# CHIP_SHIELD.net
KiCad netlist of a schematic drawn in EAGLE
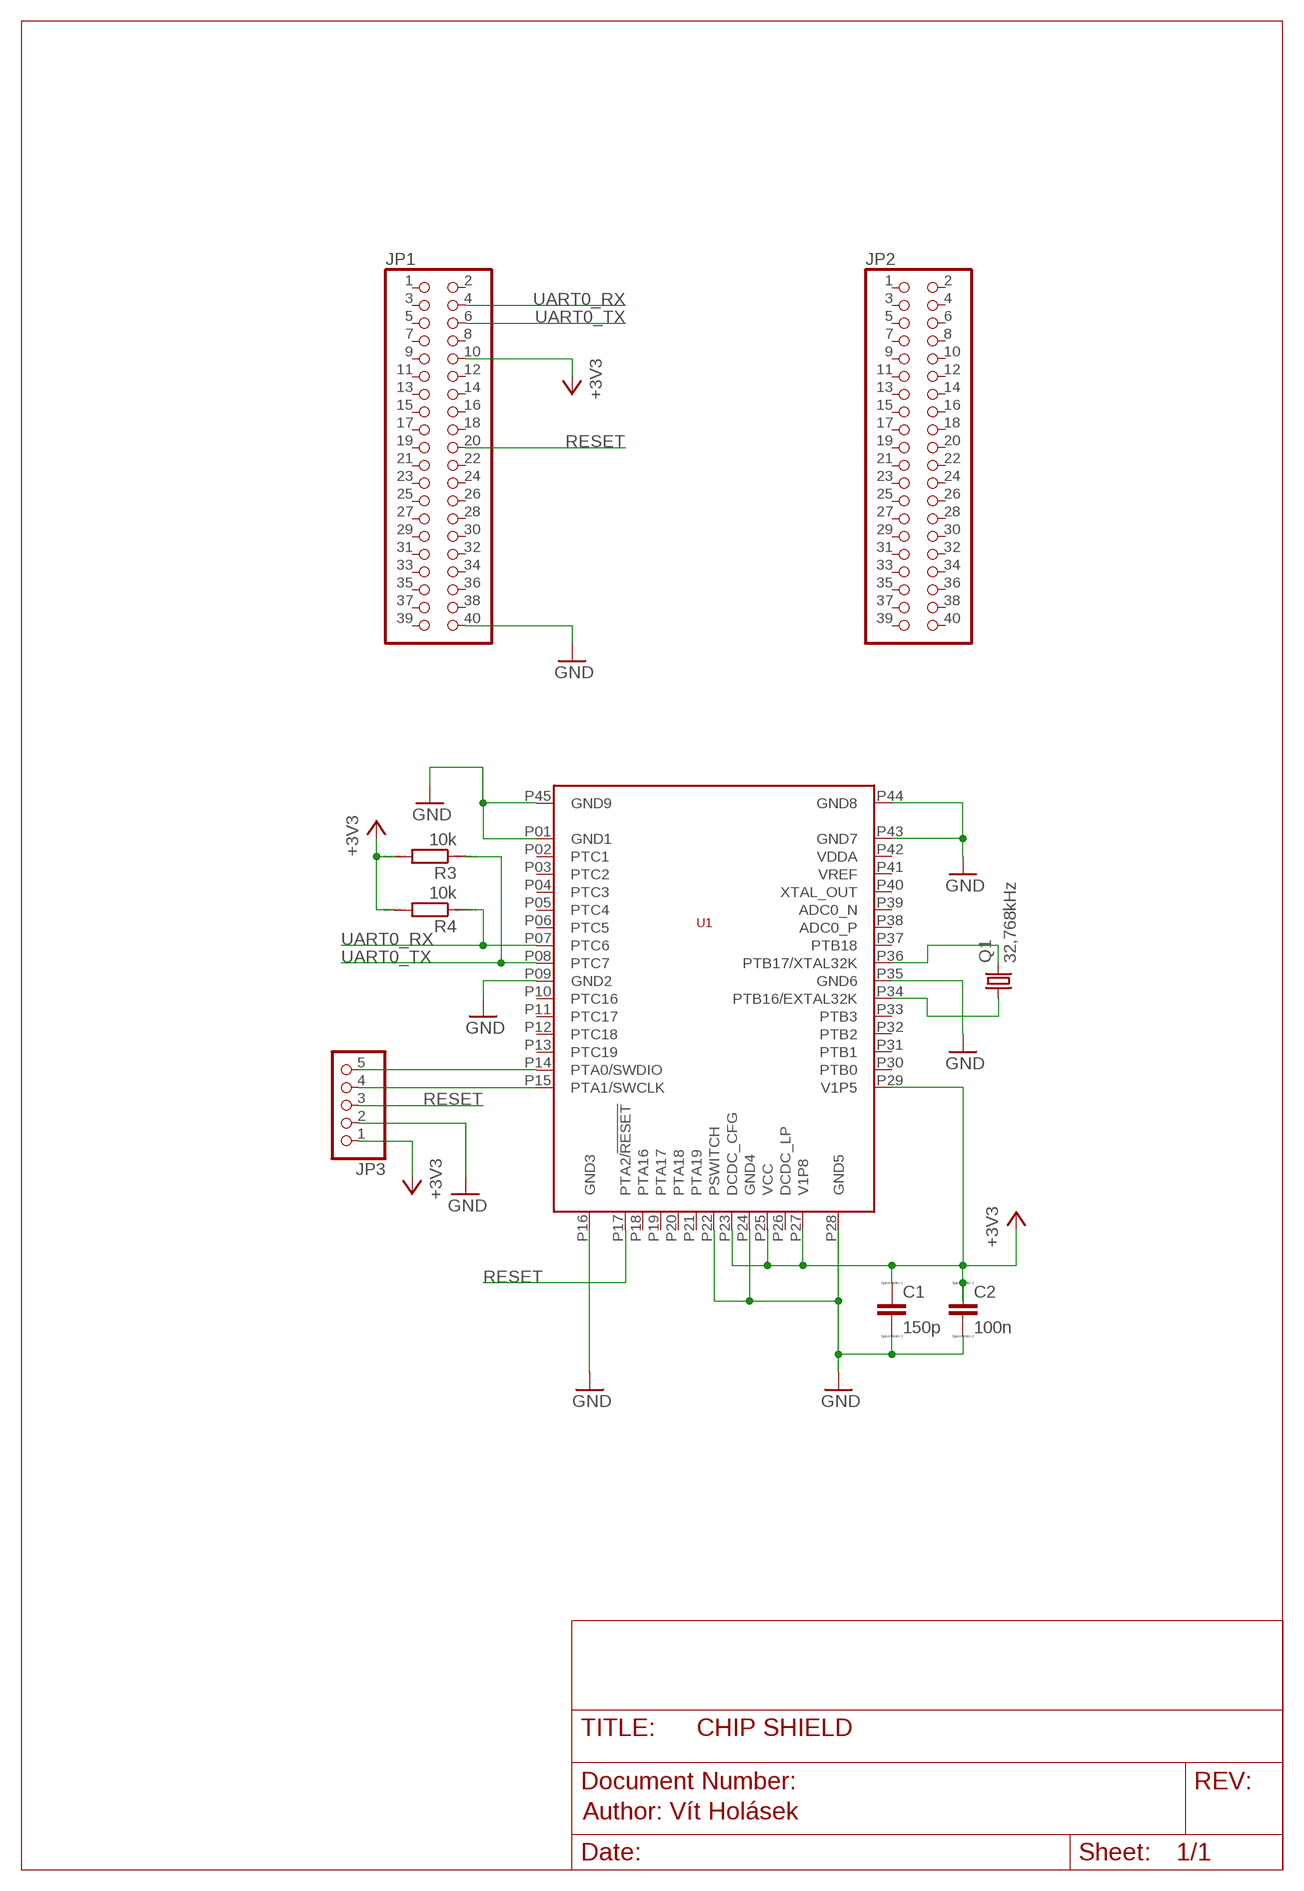
[diagram p0: schematic, sheet 1]

(export (version "E")
  (design (tool "Eeschema 10.0.6"))
  (components
    (comp (ref "C1")
      (value "150p")
      (footprint "eagle-import:C0402")
      (libsource (lib "eagle-import") (part "CC0402"))
    )
    (comp (ref "C2")
      (value "100n")
      (footprint "eagle-import:C0402")
      (libsource (lib "eagle-import") (part "CC0402"))
    )
    (comp (ref "JP1")
      (value "PINHD-2X20")
      (footprint "eagle-import:2X20")
      (libsource (lib "eagle-import") (part "PINHD-2X20"))
    )
    (comp (ref "JP2")
      (value "PINHD-2X20")
      (footprint "eagle-import:2X20")
      (libsource (lib "eagle-import") (part "PINHD-2X20"))
    )
    (comp (ref "JP3")
      (value "PINHD-1X5")
      (footprint "eagle-import:1X05")
      (libsource (lib "eagle-import") (part "PINHD-1X5"))
    )
    (comp (ref "Q1")
      (value "32,768kHz")
      (footprint "eagle-import:MC-306")
      (fields (field (name "MPN") "MC-306 60.0KHZ  100PPM ,12.5PF"))
      (libsource (lib "eagle-import") (part "MC-306"))
    )
    (comp (ref "R3")
      (value "10k")
      (footprint "eagle-import:R0402")
      (libsource (lib "eagle-import") (part "RR0402"))
    )
    (comp (ref "R4")
      (value "10k")
      (footprint "eagle-import:R0402")
      (libsource (lib "eagle-import") (part "RR0402"))
    )
    (comp (ref "U1")
      (value "R41Z-T")
      (footprint "eagle-import:R41Z")
      (libsource (lib "eagle-import") (part "R41Z-T"))
    )
  )
  (nets
    (net (code "1") (name "+3V3") (class "Default")
      (node (ref "C1") (pin "1") (pinfunction "1_1") (pintype "passive"))
      (node (ref "C2") (pin "1") (pinfunction "1_1") (pintype "passive"))
      (node (ref "JP1") (pin "10") (pinfunction "10_10") (pintype "passive"))
      (node (ref "JP3") (pin "1") (pinfunction "1_1") (pintype "passive"))
      (node (ref "R3") (pin "2") (pinfunction "2_2") (pintype "passive"))
      (node (ref "R4") (pin "2") (pinfunction "2_2") (pintype "passive"))
      (node (ref "U1") (pin "P23") (pinfunction "DCDC_CFG_P23") (pintype "bidirectional"))
      (node (ref "U1") (pin "P25") (pinfunction "VCC_P25") (pintype "bidirectional"))
      (node (ref "U1") (pin "P27") (pinfunction "V1P8_P27") (pintype "bidirectional"))
      (node (ref "U1") (pin "P29") (pinfunction "V1P5_P29") (pintype "bidirectional"))
    )
    (net (code "2") (name "/RESET") (class "Default")
      (node (ref "JP1") (pin "20") (pinfunction "20_20") (pintype "passive"))
      (node (ref "JP3") (pin "3") (pinfunction "3_3") (pintype "passive"))
      (node (ref "U1") (pin "P17") (pinfunction "PTA2/~{RESET}_P17") (pintype "bidirectional"))
    )
    (net (code "3") (name "/UART0_RX") (class "Default")
      (node (ref "JP1") (pin "4") (pinfunction "4_4") (pintype "passive"))
      (node (ref "R4") (pin "1") (pinfunction "1_1") (pintype "passive"))
      (node (ref "U1") (pin "P07") (pinfunction "PTC6_P07") (pintype "bidirectional"))
    )
    (net (code "4") (name "/UART0_TX") (class "Default")
      (node (ref "JP1") (pin "6") (pinfunction "6_6") (pintype "passive"))
      (node (ref "R3") (pin "1") (pinfunction "1_1") (pintype "passive"))
      (node (ref "U1") (pin "P08") (pinfunction "PTC7_P08") (pintype "bidirectional"))
    )
    (net (code "5") (name "GND") (class "Default")
      (node (ref "C1") (pin "2") (pinfunction "2_2") (pintype "passive"))
      (node (ref "C2") (pin "2") (pinfunction "2_2") (pintype "passive"))
      (node (ref "JP1") (pin "40") (pinfunction "40_40") (pintype "passive"))
      (node (ref "JP3") (pin "2") (pinfunction "2_2") (pintype "passive"))
      (node (ref "U1") (pin "P01") (pinfunction "GND1_P01") (pintype "bidirectional"))
      (node (ref "U1") (pin "P09") (pinfunction "GND2_P09") (pintype "bidirectional"))
      (node (ref "U1") (pin "P16") (pinfunction "GND3_P16") (pintype "bidirectional"))
      (node (ref "U1") (pin "P22") (pinfunction "PSWITCH_P22") (pintype "bidirectional"))
      (node (ref "U1") (pin "P24") (pinfunction "GND4_P24") (pintype "bidirectional"))
      (node (ref "U1") (pin "P28") (pinfunction "GND5_P28") (pintype "bidirectional"))
      (node (ref "U1") (pin "P35") (pinfunction "GND6_P35") (pintype "bidirectional"))
      (node (ref "U1") (pin "P43") (pinfunction "GND7_P43") (pintype "bidirectional"))
      (node (ref "U1") (pin "P44") (pinfunction "GND8_P44") (pintype "bidirectional"))
      (node (ref "U1") (pin "P45") (pinfunction "GND9_P45") (pintype "bidirectional"))
    )
    (net (code "6") (name "Net-(Q1-2)") (class "Default")
      (node (ref "Q1") (pin "4") (pinfunction "2_4") (pintype "passive"))
      (node (ref "U1") (pin "P36") (pinfunction "PTB17/XTAL32K_P36") (pintype "bidirectional"))
    )
    (net (code "7") (name "Net-(U1-PTA0{slash}SWDIO)") (class "Default")
      (node (ref "JP3") (pin "5") (pinfunction "5_5") (pintype "passive"))
      (node (ref "U1") (pin "P14") (pinfunction "PTA0/SWDIO_P14") (pintype "bidirectional"))
    )
    (net (code "8") (name "Net-(U1-PTA1{slash}SWCLK)") (class "Default")
      (node (ref "JP3") (pin "4") (pinfunction "4_4") (pintype "passive"))
      (node (ref "U1") (pin "P15") (pinfunction "PTA1/SWCLK_P15") (pintype "bidirectional"))
    )
    (net (code "9") (name "Net-(U1-PTB16{slash}EXTAL32K)") (class "Default")
      (node (ref "Q1") (pin "1") (pinfunction "1_1") (pintype "passive"))
      (node (ref "U1") (pin "P34") (pinfunction "PTB16/EXTAL32K_P34") (pintype "bidirectional"))
    )
    (net (code "10") (name "unconnected-(JP1-Pad1)") (class "Default")
      (node (ref "JP1") (pin "1") (pinfunction "1_1") (pintype "passive"))
    )
    (net (code "11") (name "unconnected-(JP1-Pad2)") (class "Default")
      (node (ref "JP1") (pin "2") (pinfunction "2_2") (pintype "passive"))
    )
    (net (code "12") (name "unconnected-(JP1-Pad3)") (class "Default")
      (node (ref "JP1") (pin "3") (pinfunction "3_3") (pintype "passive"))
    )
    (net (code "13") (name "unconnected-(JP1-Pad5)") (class "Default")
      (node (ref "JP1") (pin "5") (pinfunction "5_5") (pintype "passive"))
    )
    (net (code "14") (name "unconnected-(JP1-Pad7)") (class "Default")
      (node (ref "JP1") (pin "7") (pinfunction "7_7") (pintype "passive"))
    )
    (net (code "15") (name "unconnected-(JP1-Pad8)") (class "Default")
      (node (ref "JP1") (pin "8") (pinfunction "8_8") (pintype "passive"))
    )
    (net (code "16") (name "unconnected-(JP1-Pad9)") (class "Default")
      (node (ref "JP1") (pin "9") (pinfunction "9_9") (pintype "passive"))
    )
    (net (code "17") (name "unconnected-(JP1-Pad11)") (class "Default")
      (node (ref "JP1") (pin "11") (pinfunction "11_11") (pintype "passive"))
    )
    (net (code "18") (name "unconnected-(JP1-Pad12)") (class "Default")
      (node (ref "JP1") (pin "12") (pinfunction "12_12") (pintype "passive"))
    )
    (net (code "19") (name "unconnected-(JP1-Pad13)") (class "Default")
      (node (ref "JP1") (pin "13") (pinfunction "13_13") (pintype "passive"))
    )
    (net (code "20") (name "unconnected-(JP1-Pad14)") (class "Default")
      (node (ref "JP1") (pin "14") (pinfunction "14_14") (pintype "passive"))
    )
    (net (code "21") (name "unconnected-(JP1-Pad15)") (class "Default")
      (node (ref "JP1") (pin "15") (pinfunction "15_15") (pintype "passive"))
    )
    (net (code "22") (name "unconnected-(JP1-Pad16)") (class "Default")
      (node (ref "JP1") (pin "16") (pinfunction "16_16") (pintype "passive"))
    )
    (net (code "23") (name "unconnected-(JP1-Pad17)") (class "Default")
      (node (ref "JP1") (pin "17") (pinfunction "17_17") (pintype "passive"))
    )
    (net (code "24") (name "unconnected-(JP1-Pad18)") (class "Default")
      (node (ref "JP1") (pin "18") (pinfunction "18_18") (pintype "passive"))
    )
    (net (code "25") (name "unconnected-(JP1-Pad19)") (class "Default")
      (node (ref "JP1") (pin "19") (pinfunction "19_19") (pintype "passive"))
    )
    (net (code "26") (name "unconnected-(JP1-Pad21)") (class "Default")
      (node (ref "JP1") (pin "21") (pinfunction "21_21") (pintype "passive"))
    )
    (net (code "27") (name "unconnected-(JP1-Pad22)") (class "Default")
      (node (ref "JP1") (pin "22") (pinfunction "22_22") (pintype "passive"))
    )
    (net (code "28") (name "unconnected-(JP1-Pad23)") (class "Default")
      (node (ref "JP1") (pin "23") (pinfunction "23_23") (pintype "passive"))
    )
    (net (code "29") (name "unconnected-(JP1-Pad24)") (class "Default")
      (node (ref "JP1") (pin "24") (pinfunction "24_24") (pintype "passive"))
    )
    (net (code "30") (name "unconnected-(JP1-Pad25)") (class "Default")
      (node (ref "JP1") (pin "25") (pinfunction "25_25") (pintype "passive"))
    )
    (net (code "31") (name "unconnected-(JP1-Pad26)") (class "Default")
      (node (ref "JP1") (pin "26") (pinfunction "26_26") (pintype "passive"))
    )
    (net (code "32") (name "unconnected-(JP1-Pad27)") (class "Default")
      (node (ref "JP1") (pin "27") (pinfunction "27_27") (pintype "passive"))
    )
    (net (code "33") (name "unconnected-(JP1-Pad28)") (class "Default")
      (node (ref "JP1") (pin "28") (pinfunction "28_28") (pintype "passive"))
    )
    (net (code "34") (name "unconnected-(JP1-Pad29)") (class "Default")
      (node (ref "JP1") (pin "29") (pinfunction "29_29") (pintype "passive"))
    )
    (net (code "35") (name "unconnected-(JP1-Pad30)") (class "Default")
      (node (ref "JP1") (pin "30") (pinfunction "30_30") (pintype "passive"))
    )
    (net (code "36") (name "unconnected-(JP1-Pad31)") (class "Default")
      (node (ref "JP1") (pin "31") (pinfunction "31_31") (pintype "passive"))
    )
    (net (code "37") (name "unconnected-(JP1-Pad32)") (class "Default")
      (node (ref "JP1") (pin "32") (pinfunction "32_32") (pintype "passive"))
    )
    (net (code "38") (name "unconnected-(JP1-Pad33)") (class "Default")
      (node (ref "JP1") (pin "33") (pinfunction "33_33") (pintype "passive"))
    )
    (net (code "39") (name "unconnected-(JP1-Pad34)") (class "Default")
      (node (ref "JP1") (pin "34") (pinfunction "34_34") (pintype "passive"))
    )
    (net (code "40") (name "unconnected-(JP1-Pad35)") (class "Default")
      (node (ref "JP1") (pin "35") (pinfunction "35_35") (pintype "passive"))
    )
    (net (code "41") (name "unconnected-(JP1-Pad36)") (class "Default")
      (node (ref "JP1") (pin "36") (pinfunction "36_36") (pintype "passive"))
    )
    (net (code "42") (name "unconnected-(JP1-Pad37)") (class "Default")
      (node (ref "JP1") (pin "37") (pinfunction "37_37") (pintype "passive"))
    )
    (net (code "43") (name "unconnected-(JP1-Pad38)") (class "Default")
      (node (ref "JP1") (pin "38") (pinfunction "38_38") (pintype "passive"))
    )
    (net (code "44") (name "unconnected-(JP1-Pad39)") (class "Default")
      (node (ref "JP1") (pin "39") (pinfunction "39_39") (pintype "passive"))
    )
    (net (code "45") (name "unconnected-(JP2-Pad1)") (class "Default")
      (node (ref "JP2") (pin "1") (pinfunction "1_1") (pintype "passive"))
    )
    (net (code "46") (name "unconnected-(JP2-Pad2)") (class "Default")
      (node (ref "JP2") (pin "2") (pinfunction "2_2") (pintype "passive"))
    )
    (net (code "47") (name "unconnected-(JP2-Pad3)") (class "Default")
      (node (ref "JP2") (pin "3") (pinfunction "3_3") (pintype "passive"))
    )
    (net (code "48") (name "unconnected-(JP2-Pad4)") (class "Default")
      (node (ref "JP2") (pin "4") (pinfunction "4_4") (pintype "passive"))
    )
    (net (code "49") (name "unconnected-(JP2-Pad5)") (class "Default")
      (node (ref "JP2") (pin "5") (pinfunction "5_5") (pintype "passive"))
    )
    (net (code "50") (name "unconnected-(JP2-Pad6)") (class "Default")
      (node (ref "JP2") (pin "6") (pinfunction "6_6") (pintype "passive"))
    )
    (net (code "51") (name "unconnected-(JP2-Pad7)") (class "Default")
      (node (ref "JP2") (pin "7") (pinfunction "7_7") (pintype "passive"))
    )
    (net (code "52") (name "unconnected-(JP2-Pad8)") (class "Default")
      (node (ref "JP2") (pin "8") (pinfunction "8_8") (pintype "passive"))
    )
    (net (code "53") (name "unconnected-(JP2-Pad9)") (class "Default")
      (node (ref "JP2") (pin "9") (pinfunction "9_9") (pintype "passive"))
    )
    (net (code "54") (name "unconnected-(JP2-Pad10)") (class "Default")
      (node (ref "JP2") (pin "10") (pinfunction "10_10") (pintype "passive"))
    )
    (net (code "55") (name "unconnected-(JP2-Pad11)") (class "Default")
      (node (ref "JP2") (pin "11") (pinfunction "11_11") (pintype "passive"))
    )
    (net (code "56") (name "unconnected-(JP2-Pad12)") (class "Default")
      (node (ref "JP2") (pin "12") (pinfunction "12_12") (pintype "passive"))
    )
    (net (code "57") (name "unconnected-(JP2-Pad13)") (class "Default")
      (node (ref "JP2") (pin "13") (pinfunction "13_13") (pintype "passive"))
    )
    (net (code "58") (name "unconnected-(JP2-Pad14)") (class "Default")
      (node (ref "JP2") (pin "14") (pinfunction "14_14") (pintype "passive"))
    )
    (net (code "59") (name "unconnected-(JP2-Pad15)") (class "Default")
      (node (ref "JP2") (pin "15") (pinfunction "15_15") (pintype "passive"))
    )
    (net (code "60") (name "unconnected-(JP2-Pad16)") (class "Default")
      (node (ref "JP2") (pin "16") (pinfunction "16_16") (pintype "passive"))
    )
    (net (code "61") (name "unconnected-(JP2-Pad17)") (class "Default")
      (node (ref "JP2") (pin "17") (pinfunction "17_17") (pintype "passive"))
    )
    (net (code "62") (name "unconnected-(JP2-Pad18)") (class "Default")
      (node (ref "JP2") (pin "18") (pinfunction "18_18") (pintype "passive"))
    )
    (net (code "63") (name "unconnected-(JP2-Pad19)") (class "Default")
      (node (ref "JP2") (pin "19") (pinfunction "19_19") (pintype "passive"))
    )
    (net (code "64") (name "unconnected-(JP2-Pad20)") (class "Default")
      (node (ref "JP2") (pin "20") (pinfunction "20_20") (pintype "passive"))
    )
    (net (code "65") (name "unconnected-(JP2-Pad21)") (class "Default")
      (node (ref "JP2") (pin "21") (pinfunction "21_21") (pintype "passive"))
    )
    (net (code "66") (name "unconnected-(JP2-Pad22)") (class "Default")
      (node (ref "JP2") (pin "22") (pinfunction "22_22") (pintype "passive"))
    )
    (net (code "67") (name "unconnected-(JP2-Pad23)") (class "Default")
      (node (ref "JP2") (pin "23") (pinfunction "23_23") (pintype "passive"))
    )
    (net (code "68") (name "unconnected-(JP2-Pad24)") (class "Default")
      (node (ref "JP2") (pin "24") (pinfunction "24_24") (pintype "passive"))
    )
    (net (code "69") (name "unconnected-(JP2-Pad25)") (class "Default")
      (node (ref "JP2") (pin "25") (pinfunction "25_25") (pintype "passive"))
    )
    (net (code "70") (name "unconnected-(JP2-Pad26)") (class "Default")
      (node (ref "JP2") (pin "26") (pinfunction "26_26") (pintype "passive"))
    )
    (net (code "71") (name "unconnected-(JP2-Pad27)") (class "Default")
      (node (ref "JP2") (pin "27") (pinfunction "27_27") (pintype "passive"))
    )
    (net (code "72") (name "unconnected-(JP2-Pad28)") (class "Default")
      (node (ref "JP2") (pin "28") (pinfunction "28_28") (pintype "passive"))
    )
    (net (code "73") (name "unconnected-(JP2-Pad29)") (class "Default")
      (node (ref "JP2") (pin "29") (pinfunction "29_29") (pintype "passive"))
    )
    (net (code "74") (name "unconnected-(JP2-Pad30)") (class "Default")
      (node (ref "JP2") (pin "30") (pinfunction "30_30") (pintype "passive"))
    )
    (net (code "75") (name "unconnected-(JP2-Pad31)") (class "Default")
      (node (ref "JP2") (pin "31") (pinfunction "31_31") (pintype "passive"))
    )
    (net (code "76") (name "unconnected-(JP2-Pad32)") (class "Default")
      (node (ref "JP2") (pin "32") (pinfunction "32_32") (pintype "passive"))
    )
    (net (code "77") (name "unconnected-(JP2-Pad33)") (class "Default")
      (node (ref "JP2") (pin "33") (pinfunction "33_33") (pintype "passive"))
    )
    (net (code "78") (name "unconnected-(JP2-Pad34)") (class "Default")
      (node (ref "JP2") (pin "34") (pinfunction "34_34") (pintype "passive"))
    )
    (net (code "79") (name "unconnected-(JP2-Pad35)") (class "Default")
      (node (ref "JP2") (pin "35") (pinfunction "35_35") (pintype "passive"))
    )
    (net (code "80") (name "unconnected-(JP2-Pad36)") (class "Default")
      (node (ref "JP2") (pin "36") (pinfunction "36_36") (pintype "passive"))
    )
    (net (code "81") (name "unconnected-(JP2-Pad37)") (class "Default")
      (node (ref "JP2") (pin "37") (pinfunction "37_37") (pintype "passive"))
    )
    (net (code "82") (name "unconnected-(JP2-Pad38)") (class "Default")
      (node (ref "JP2") (pin "38") (pinfunction "38_38") (pintype "passive"))
    )
    (net (code "83") (name "unconnected-(JP2-Pad39)") (class "Default")
      (node (ref "JP2") (pin "39") (pinfunction "39_39") (pintype "passive"))
    )
    (net (code "84") (name "unconnected-(JP2-Pad40)") (class "Default")
      (node (ref "JP2") (pin "40") (pinfunction "40_40") (pintype "passive"))
    )
    (net (code "85") (name "unconnected-(U1-ADC0_N-PadP39)") (class "Default")
      (node (ref "U1") (pin "P39") (pinfunction "ADC0_N_P39") (pintype "bidirectional"))
    )
    (net (code "86") (name "unconnected-(U1-ADC0_P-PadP38)") (class "Default")
      (node (ref "U1") (pin "P38") (pinfunction "ADC0_P_P38") (pintype "bidirectional"))
    )
    (net (code "87") (name "unconnected-(U1-DCDC_LP-PadP26)") (class "Default")
      (node (ref "U1") (pin "P26") (pinfunction "DCDC_LP_P26") (pintype "bidirectional"))
    )
    (net (code "88") (name "unconnected-(U1-PTA16-PadP18)") (class "Default")
      (node (ref "U1") (pin "P18") (pinfunction "PTA16_P18") (pintype "bidirectional"))
    )
    (net (code "89") (name "unconnected-(U1-PTA17-PadP19)") (class "Default")
      (node (ref "U1") (pin "P19") (pinfunction "PTA17_P19") (pintype "bidirectional"))
    )
    (net (code "90") (name "unconnected-(U1-PTA18-PadP20)") (class "Default")
      (node (ref "U1") (pin "P20") (pinfunction "PTA18_P20") (pintype "bidirectional"))
    )
    (net (code "91") (name "unconnected-(U1-PTA19-PadP21)") (class "Default")
      (node (ref "U1") (pin "P21") (pinfunction "PTA19_P21") (pintype "bidirectional"))
    )
    (net (code "92") (name "unconnected-(U1-PTB0-PadP30)") (class "Default")
      (node (ref "U1") (pin "P30") (pinfunction "PTB0_P30") (pintype "bidirectional"))
    )
    (net (code "93") (name "unconnected-(U1-PTB1-PadP31)") (class "Default")
      (node (ref "U1") (pin "P31") (pinfunction "PTB1_P31") (pintype "bidirectional"))
    )
    (net (code "94") (name "unconnected-(U1-PTB2-PadP32)") (class "Default")
      (node (ref "U1") (pin "P32") (pinfunction "PTB2_P32") (pintype "bidirectional"))
    )
    (net (code "95") (name "unconnected-(U1-PTB3-PadP33)") (class "Default")
      (node (ref "U1") (pin "P33") (pinfunction "PTB3_P33") (pintype "bidirectional"))
    )
    (net (code "96") (name "unconnected-(U1-PTB18-PadP37)") (class "Default")
      (node (ref "U1") (pin "P37") (pinfunction "PTB18_P37") (pintype "bidirectional"))
    )
    (net (code "97") (name "unconnected-(U1-PTC1-PadP02)") (class "Default")
      (node (ref "U1") (pin "P02") (pinfunction "PTC1_P02") (pintype "bidirectional"))
    )
    (net (code "98") (name "unconnected-(U1-PTC2-PadP03)") (class "Default")
      (node (ref "U1") (pin "P03") (pinfunction "PTC2_P03") (pintype "bidirectional"))
    )
    (net (code "99") (name "unconnected-(U1-PTC3-PadP04)") (class "Default")
      (node (ref "U1") (pin "P04") (pinfunction "PTC3_P04") (pintype "bidirectional"))
    )
    (net (code "100") (name "unconnected-(U1-PTC4-PadP05)") (class "Default")
      (node (ref "U1") (pin "P05") (pinfunction "PTC4_P05") (pintype "bidirectional"))
    )
    (net (code "101") (name "unconnected-(U1-PTC5-PadP06)") (class "Default")
      (node (ref "U1") (pin "P06") (pinfunction "PTC5_P06") (pintype "bidirectional"))
    )
    (net (code "102") (name "unconnected-(U1-PTC16-PadP10)") (class "Default")
      (node (ref "U1") (pin "P10") (pinfunction "PTC16_P10") (pintype "bidirectional"))
    )
    (net (code "103") (name "unconnected-(U1-PTC17-PadP11)") (class "Default")
      (node (ref "U1") (pin "P11") (pinfunction "PTC17_P11") (pintype "bidirectional"))
    )
    (net (code "104") (name "unconnected-(U1-PTC18-PadP12)") (class "Default")
      (node (ref "U1") (pin "P12") (pinfunction "PTC18_P12") (pintype "bidirectional"))
    )
    (net (code "105") (name "unconnected-(U1-PTC19-PadP13)") (class "Default")
      (node (ref "U1") (pin "P13") (pinfunction "PTC19_P13") (pintype "bidirectional"))
    )
    (net (code "106") (name "unconnected-(U1-VDDA-PadP42)") (class "Default")
      (node (ref "U1") (pin "P42") (pinfunction "VDDA_P42") (pintype "bidirectional"))
    )
    (net (code "107") (name "unconnected-(U1-VREF-PadP41)") (class "Default")
      (node (ref "U1") (pin "P41") (pinfunction "VREF_P41") (pintype "bidirectional"))
    )
    (net (code "108") (name "unconnected-(U1-XTAL_OUT-PadP40)") (class "Default")
      (node (ref "U1") (pin "P40") (pinfunction "XTAL_OUT_P40") (pintype "bidirectional"))
    )
  )
)
